# 2018_Traco12V5A.net
KiCad netlist of a schematic drawn in Altium Designer
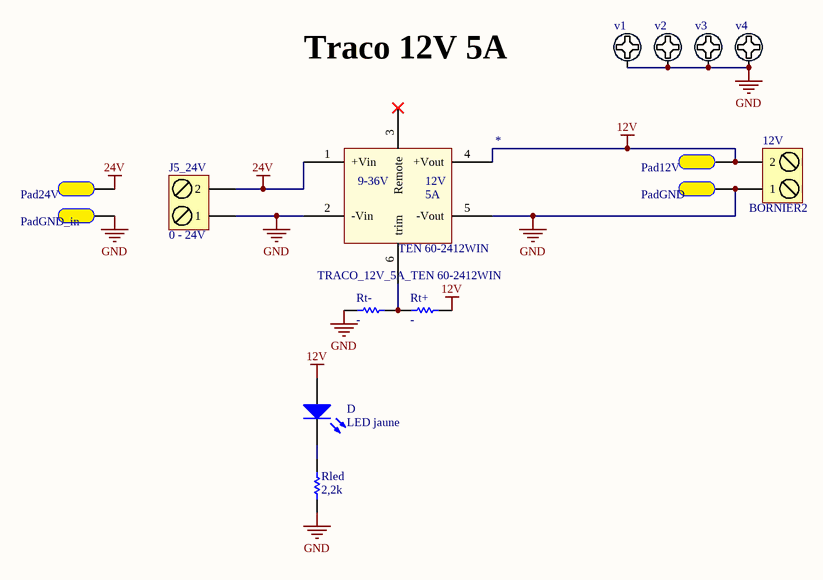
[diagram p0: 2018_Traco12V5A.SchDoc]

(export (version "E")
  (design (tool "Eeschema 10.0.6"))
  (components
    (comp (ref "*")
      (value "TRACO_12V_5A_TEN 60-2412WIN")
      (footprint "TRACO_TEN60")
      (libsource (lib "_ROBOT") (part "TRACO_12V_5A_TEN 60-2412WIN"))
    )
    (comp (ref "12V")
      (value "BORNIER2")
      (footprint "BORNIER2")
      (description "Terminal blocks, 2 pins, pitch=5mm")
      (libsource (lib "Connecteur") (part "BORNIER2"))
    )
    (comp (ref "D")
      (value "LED jaune")
      (footprint "LED_0805")
      (description "Typical LED")
      (fields (field (name "PUBLISHER") "Altium Limited"))
      (libsource (lib "_ROBOT") (part "LED"))
    )
    (comp (ref "J5_24V")
      (value "0 - 24V")
      (footprint "BORNIER2_FEM_COUDE")
      (description "Terminal blocks, 2 pins, pitch=5mm")
      (libsource (lib "miniprojet") (part "BORNIER2"))
    )
    (comp (ref "Pad12V")
      (value "Pad_CMS")
      (footprint "PAD_CMS_5.08x2.54")
      (description "Pad pour souder un fil")
      (fields (field (name "PUBLISHER") "Damien Guitton"))
      (libsource (lib "DG_Connecteur") (part "Pad_CMS"))
    )
    (comp (ref "Pad24V")
      (value "Pad_CMS")
      (footprint "PAD_CMS_5.08x2.54")
      (description "Pad pour souder un fil")
      (fields (field (name "PUBLISHER") "Damien Guitton"))
      (libsource (lib "DG_Connecteur") (part "Pad_CMS"))
    )
    (comp (ref "PadGND")
      (value "Pad_CMS")
      (footprint "PAD_CMS_5.08x2.54")
      (description "Pad pour souder un fil")
      (fields (field (name "PUBLISHER") "Damien Guitton"))
      (libsource (lib "DG_Connecteur") (part "Pad_CMS"))
    )
    (comp (ref "PadGND_in")
      (value "Pad_CMS")
      (footprint "PAD_CMS_5.08x2.54")
      (description "Pad pour souder un fil")
      (fields (field (name "PUBLISHER") "Damien Guitton"))
      (libsource (lib "DG_Connecteur") (part "Pad_CMS"))
    )
    (comp (ref "Rled")
      (value "2,2k")
      (footprint "R1206_N")
      (description "Resistor")
      (fields (field (name "PUBLISHER") "Altium Limited"))
      (libsource (lib "_ROBOT") (part "Resistor"))
    )
    (comp (ref "Rt+")
      (value "-")
      (footprint "R1206_N")
      (description "Resistor")
      (fields (field (name "PUBLISHER") "Altium Limited"))
      (libsource (lib "_ROBOT") (part "Resistor"))
    )
    (comp (ref "Rt-")
      (value "-")
      (footprint "R1206_N")
      (description "Resistor")
      (fields (field (name "PUBLISHER") "Altium Limited"))
      (libsource (lib "_ROBOT") (part "Resistor"))
    )
    (comp (ref "v1")
      (value "Pad_M3")
      (footprint "ENTRETOISE_CMS")
      (description "Vis M3 X 6mm _TORX_Tête 6mm")
      (fields (field (name "PUBLISHER") "Damien Guitton"))
      (libsource (lib "_ROBOT") (part "Vis M3 X 6mm _TORX_Tête 6mm"))
    )
    (comp (ref "v2")
      (value "Pad_M3")
      (footprint "ENTRETOISE_CMS")
      (description "Vis M3 X 6mm _TORX_Tête 6mm")
      (fields (field (name "PUBLISHER") "Damien Guitton"))
      (libsource (lib "_ROBOT") (part "Vis M3 X 6mm _TORX_Tête 6mm"))
    )
    (comp (ref "v3")
      (value "Pad_M3")
      (footprint "ENTRETOISE_CMS")
      (description "Vis M3 X 6mm _TORX_Tête 6mm")
      (fields (field (name "PUBLISHER") "Damien Guitton"))
      (libsource (lib "_ROBOT") (part "Vis M3 X 6mm _TORX_Tête 6mm"))
    )
    (comp (ref "v4")
      (value "Pad_M3")
      (footprint "ENTRETOISE_CMS")
      (description "Vis M3 X 6mm _TORX_Tête 6mm")
      (fields (field (name "PUBLISHER") "Damien Guitton"))
      (libsource (lib "_ROBOT") (part "Vis M3 X 6mm _TORX_Tête 6mm"))
    )
  )
  (nets
    (net (code "1") (name "12V") (class "Default")
      (node (ref "*") (pin "4") (pinfunction "+Vout_4") (pintype "passive"))
      (node (ref "12V") (pin "2") (pinfunction "2_2") (pintype "passive"))
      (node (ref "D") (pin "1") (pinfunction "A_1") (pintype "passive"))
      (node (ref "Pad12V") (pin "1") (pinfunction "1_1") (pintype "passive"))
      (node (ref "Rt+") (pin "1") (pinfunction "1_1") (pintype "passive"))
    )
    (net (code "2") (name "24V") (class "Default")
      (node (ref "*") (pin "1") (pinfunction "+Vin_1") (pintype "passive"))
      (node (ref "J5_24V") (pin "2") (pinfunction "2_2") (pintype "passive"))
      (node (ref "Pad24V") (pin "1") (pinfunction "1_1") (pintype "passive"))
    )
    (net (code "3") (name "GND") (class "Default")
      (node (ref "*") (pin "2") (pinfunction "-Vin_2") (pintype "passive"))
      (node (ref "*") (pin "5") (pinfunction "-Vout_5") (pintype "passive"))
      (node (ref "12V") (pin "1") (pinfunction "1_1") (pintype "passive"))
      (node (ref "J5_24V") (pin "1") (pinfunction "1_1") (pintype "passive"))
      (node (ref "PadGND") (pin "1") (pinfunction "1_1") (pintype "passive"))
      (node (ref "PadGND_in") (pin "1") (pinfunction "1_1") (pintype "passive"))
      (node (ref "Rled") (pin "1") (pinfunction "1_1") (pintype "passive"))
      (node (ref "Rt-") (pin "2") (pinfunction "2_2") (pintype "passive"))
      (node (ref "v1") (pin "1") (pinfunction "1_1") (pintype "passive"))
      (node (ref "v2") (pin "1") (pinfunction "1_1") (pintype "passive"))
      (node (ref "v3") (pin "1") (pinfunction "1_1") (pintype "passive"))
      (node (ref "v4") (pin "1") (pinfunction "1_1") (pintype "passive"))
    )
    (net (code "4") (name "Net-(*-trim)") (class "Default")
      (node (ref "*") (pin "6") (pinfunction "trim_6") (pintype "passive"))
      (node (ref "Rt+") (pin "2") (pinfunction "2_2") (pintype "passive"))
      (node (ref "Rt-") (pin "1") (pinfunction "1_1") (pintype "passive"))
    )
    (net (code "5") (name "Net-(D-K)") (class "Default")
      (node (ref "D") (pin "2") (pinfunction "K_2") (pintype "passive"))
      (node (ref "Rled") (pin "2") (pinfunction "2_2") (pintype "passive"))
    )
    (net (code "6") (name "unconnected-(*-Remote-Pad3)") (class "Default")
      (node (ref "*") (pin "3") (pinfunction "Remote_3") (pintype "passive+no_connect"))
    )
  )
)
